# HB_Drive.net
KiCad netlist of a schematic drawn in Altium Designer
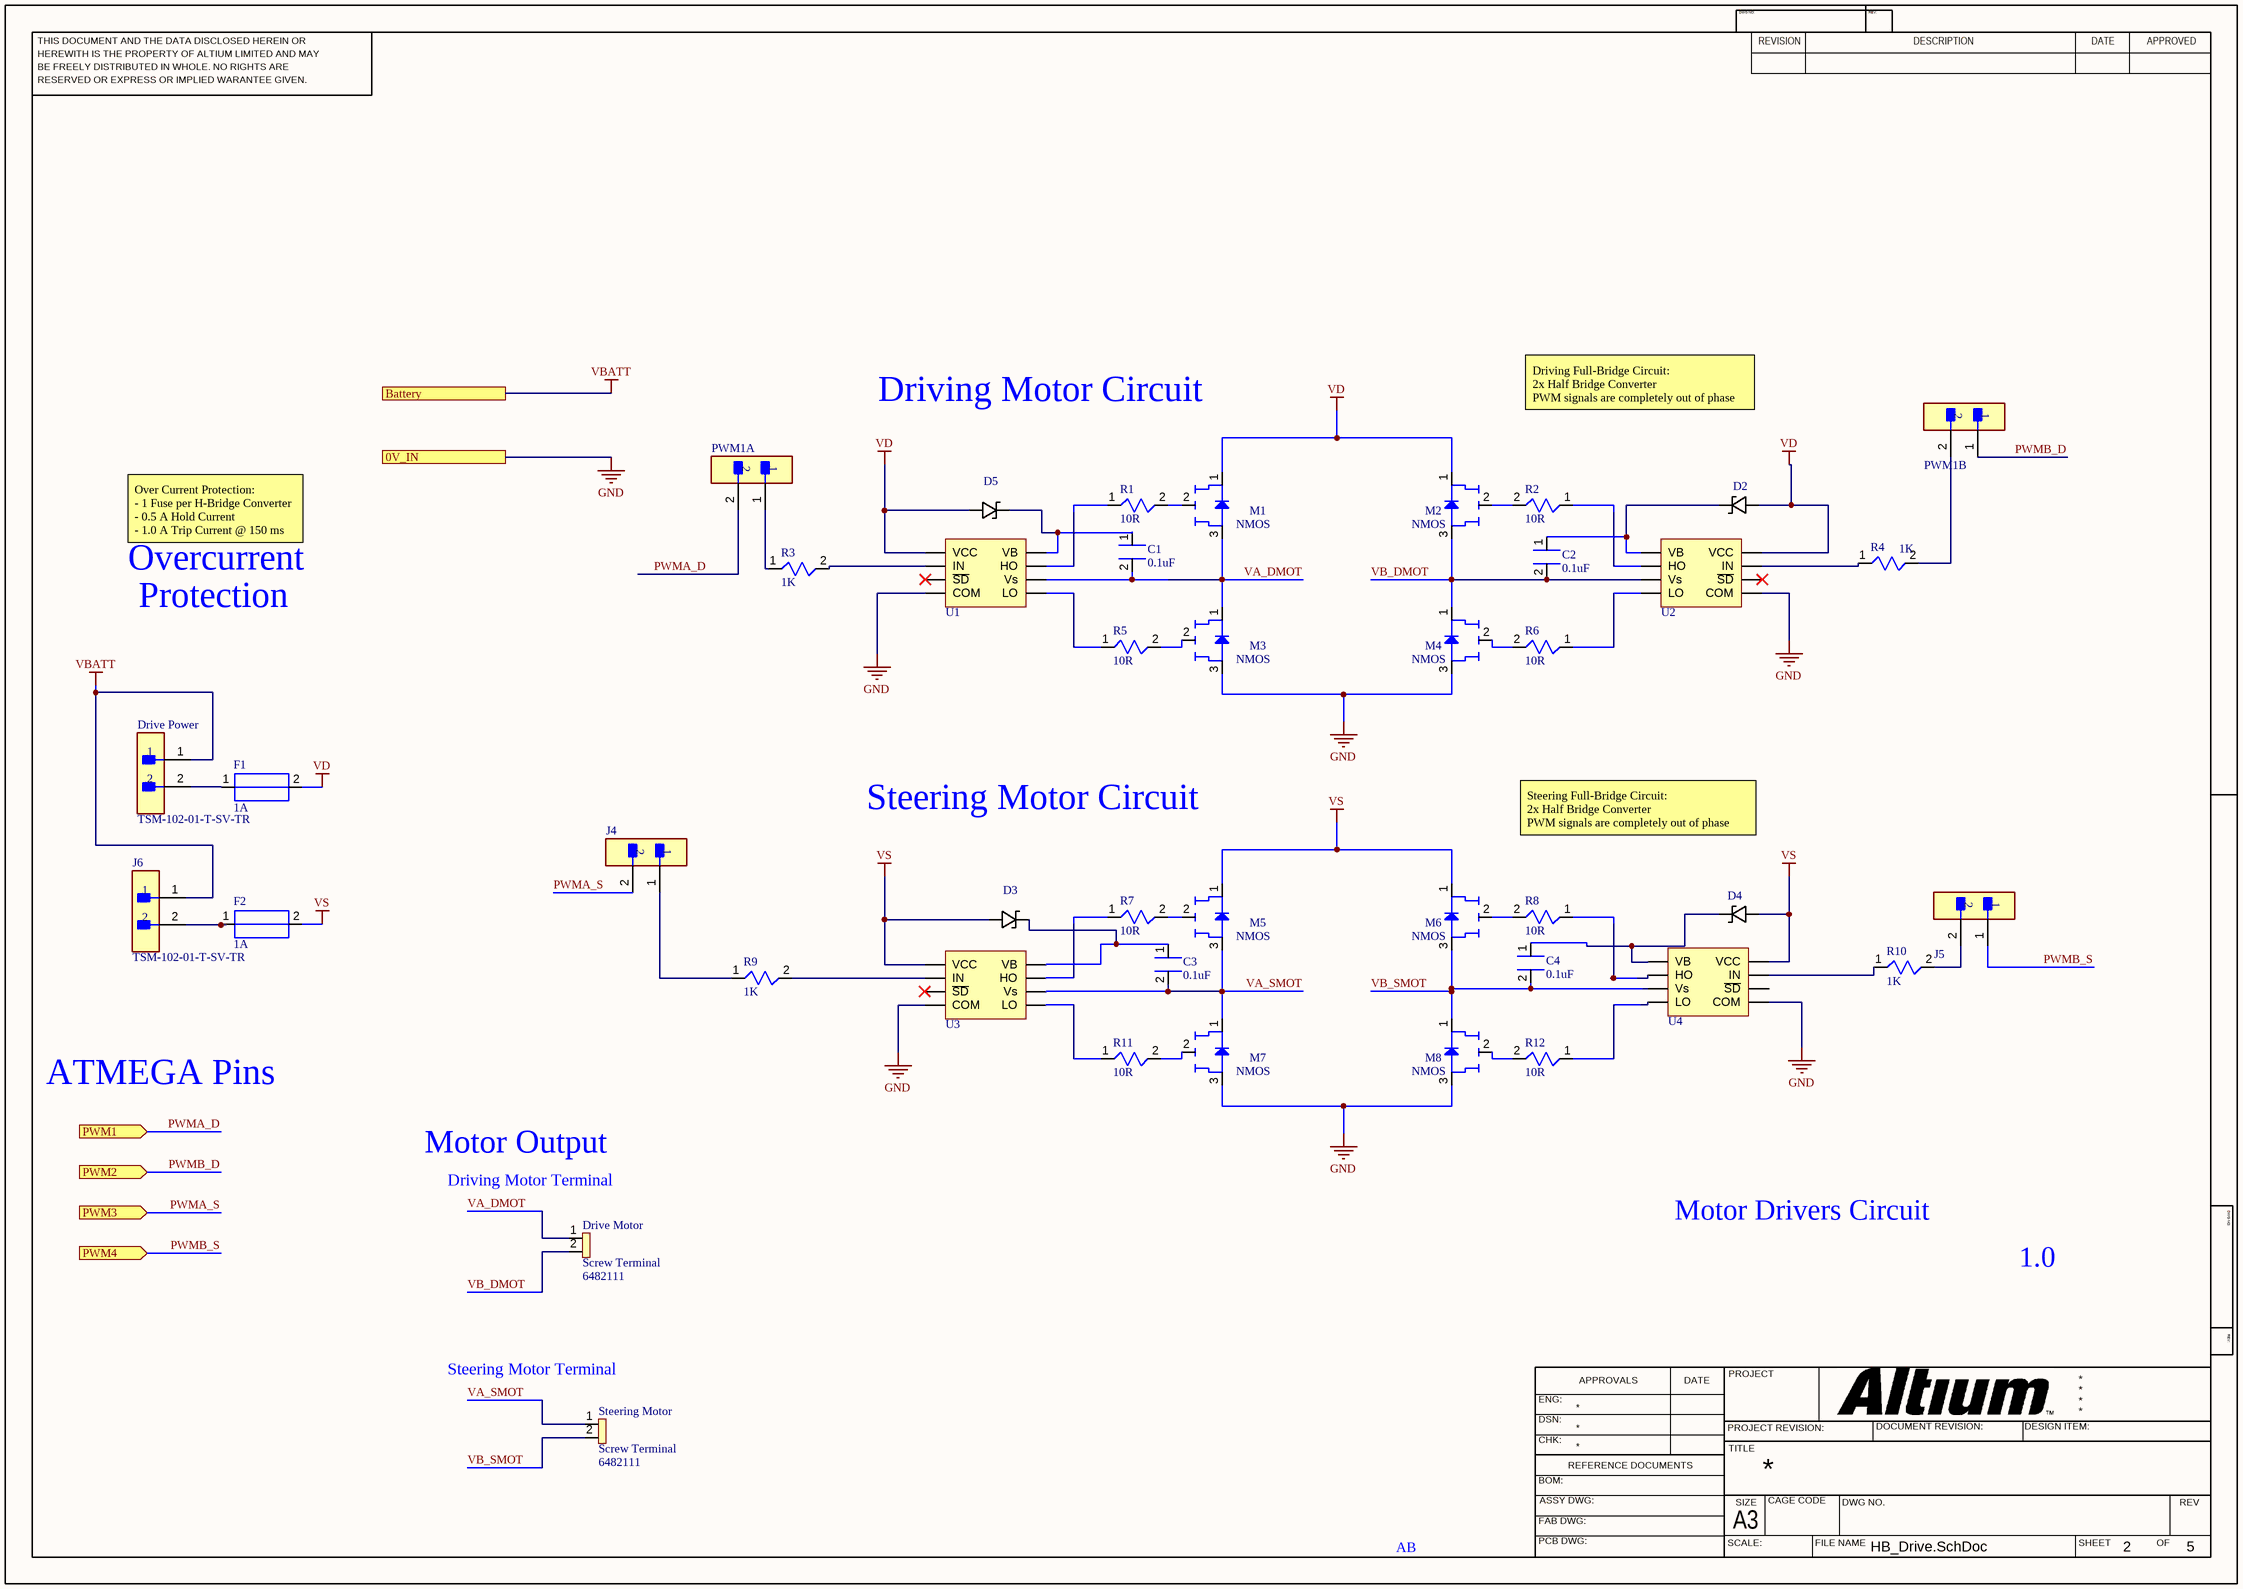
[diagram p0: HB_Drive.SchDoc]

(export (version "E")
  (design (tool "Eeschema 10.0.6"))
  (components
    (comp (ref "C1")
      (value "0.1uF")
      (footprint "0805B104K500BD")
      (description "0.1 uF 50V Cap")
      (libsource (lib "HB_Driver") (part "0805B104K500BD"))
    )
    (comp (ref "C2")
      (value "0.1uF")
      (footprint "0805B104K500BD")
      (description "0.1 uF 50V Cap")
      (libsource (lib "HB_Driver") (part "0805B104K500BD"))
    )
    (comp (ref "C3")
      (value "0.1uF")
      (footprint "0805B104K500BD")
      (description "0.1 uF 50V Cap")
      (libsource (lib "HB_Driver") (part "0805B104K500BD"))
    )
    (comp (ref "C4")
      (value "0.1uF")
      (footprint "0805B104K500BD")
      (description "0.1 uF 50V Cap")
      (libsource (lib "HB_Driver") (part "0805B104K500BD"))
    )
    (comp (ref "D2")
      (value "BAS3005B02VH6327XTSA1")
      (footprint "BAS3005B02VH6327XTSA1")
      (description "30V, Vf 620 mV @ 500 mA, 25 µA @ 30 V, Fast Recovery =< 500ns, > 200mA")
      (libsource (lib "HB_Driver") (part "BAS3005B02VH6327XTSA1"))
    )
    (comp (ref "D3")
      (value "BAS3005B02VH6327XTSA1")
      (footprint "BAS3005B02VH6327XTSA1")
      (description "30V, Vf 620 mV @ 500 mA, 25 µA @ 30 V, Fast Recovery =< 500ns, > 200mA")
      (libsource (lib "HB_Driver") (part "BAS3005B02VH6327XTSA1"))
    )
    (comp (ref "D4")
      (value "BAS3005B02VH6327XTSA1")
      (footprint "BAS3005B02VH6327XTSA1")
      (description "30V, Vf 620 mV @ 500 mA, 25 µA @ 30 V, Fast Recovery =< 500ns, > 200mA")
      (libsource (lib "HB_Driver") (part "BAS3005B02VH6327XTSA1"))
    )
    (comp (ref "D5")
      (value "BAS3005B02VH6327XTSA1")
      (footprint "BAS3005B02VH6327XTSA1")
      (description "30V, Vf 620 mV @ 500 mA, 25 µA @ 30 V, Fast Recovery =< 500ns, > 200mA")
      (libsource (lib "HB_Driver") (part "BAS3005B02VH6327XTSA1"))
    )
    (comp (ref "Drive Motor")
      (value "Screw Terminal")
      (footprint "ERM BLOCK 2POS 45DEG 2.5MM PCB")
      (fields (field (name "SUPPLIER PART NUMBER 1") "6482111"))
      (libsource (lib "HB_Driver") (part "ERM BLOCK 2POS 45DEG 2.5MM PCB"))
    )
    (comp (ref "Drive Power")
      (value "TSM-102-01-T-SV-TR")
      (footprint "FP-TSM-102-01-T-SV-TR-MFG")
      (description "CONN HEADER SMD 2POS 2.54MM")
      (libsource (lib "") (part "3bc925449376181038e59eaffc5286c_1"))
    )
    (comp (ref "F1")
      (value "1A")
      (footprint "0ZCG0050AF2C")
      (description "PTC Resettable Fuse 0.5A(hold) 1A(trip) 30VDC 100A 0.8W 0.15s 0.15Ohm SMD Solder Pad 1812 T/R")
      (fields (field (name "MANUFACTURER") "Bel") (field (name "MANUFACTURER PART NUMBER") "0ZCG0050AF2C"))
      (libsource (lib "HB_Driver") (part "0ZCG0050AF2C"))
    )
    (comp (ref "F2")
      (value "1A")
      (footprint "0ZCG0050AF2C")
      (description "PTC Resettable Fuse 0.5A(hold) 1A(trip) 30VDC 100A 0.8W 0.15s 0.15Ohm SMD Solder Pad 1812 T/R")
      (fields (field (name "MANUFACTURER") "Bel") (field (name "MANUFACTURER PART NUMBER") "0ZCG0050AF2C"))
      (libsource (lib "HB_Driver") (part "0ZCG0050AF2C"))
    )
    (comp (ref "J4")
      (value "TSM-102-01-T-SV-TR")
      (footprint "FP-TSM-102-01-T-SV-TR-MFG")
      (description "CONN HEADER SMD 2POS 2.54MM")
      (libsource (lib "Altium Content Vault") (part "3bc925449376181038e59eaffc5286c"))
    )
    (comp (ref "J5")
      (value "TSM-102-01-T-SV-TR")
      (footprint "FP-TSM-102-01-T-SV-TR-MFG")
      (description "CONN HEADER SMD 2POS 2.54MM")
      (libsource (lib "Altium Content Vault") (part "3bc925449376181038e59eaffc5286c"))
    )
    (comp (ref "J6")
      (value "TSM-102-01-T-SV-TR")
      (footprint "FP-TSM-102-01-T-SV-TR-MFG")
      (description "CONN HEADER SMD 2POS 2.54MM")
      (libsource (lib "") (part "3bc925449376181038e59eaffc5286c_1"))
    )
    (comp (ref "M1")
      (value "NMOS")
      (footprint "AOD424")
      (description "MOSFET N-CH 20V 18A TO252")
      (fields
        (field (name "MANUFACTURER") "Alpha & Omega Semiconductor")
        (field (name "MANUFACTURER PART NUMBER") "AOD424")
      )
      (libsource (lib "HB_Driver") (part "AOD424"))
    )
    (comp (ref "M2")
      (value "NMOS")
      (footprint "AOD424")
      (description "MOSFET N-CH 20V 18A TO252")
      (fields
        (field (name "MANUFACTURER") "Alpha & Omega Semiconductor")
        (field (name "MANUFACTURER PART NUMBER") "AOD424")
      )
      (libsource (lib "HB_Driver") (part "AOD424"))
    )
    (comp (ref "M3")
      (value "NMOS")
      (footprint "AOD424")
      (description "MOSFET N-CH 20V 18A TO252")
      (fields
        (field (name "MANUFACTURER") "Alpha & Omega Semiconductor")
        (field (name "MANUFACTURER PART NUMBER") "AOD424")
      )
      (libsource (lib "HB_Driver") (part "AOD424"))
    )
    (comp (ref "M4")
      (value "NMOS")
      (footprint "AOD424")
      (description "MOSFET N-CH 20V 18A TO252")
      (fields
        (field (name "MANUFACTURER") "Alpha & Omega Semiconductor")
        (field (name "MANUFACTURER PART NUMBER") "AOD424")
      )
      (libsource (lib "HB_Driver") (part "AOD424"))
    )
    (comp (ref "M5")
      (value "NMOS")
      (footprint "AOD424")
      (description "MOSFET N-CH 20V 18A TO252")
      (fields
        (field (name "MANUFACTURER") "Alpha & Omega Semiconductor")
        (field (name "MANUFACTURER PART NUMBER") "AOD424")
      )
      (libsource (lib "HB_Driver") (part "AOD424"))
    )
    (comp (ref "M6")
      (value "NMOS")
      (footprint "AOD424")
      (description "MOSFET N-CH 20V 18A TO252")
      (fields
        (field (name "MANUFACTURER") "Alpha & Omega Semiconductor")
        (field (name "MANUFACTURER PART NUMBER") "AOD424")
      )
      (libsource (lib "HB_Driver") (part "AOD424"))
    )
    (comp (ref "M7")
      (value "NMOS")
      (footprint "AOD424")
      (description "MOSFET N-CH 20V 18A TO252")
      (fields
        (field (name "MANUFACTURER") "Alpha & Omega Semiconductor")
        (field (name "MANUFACTURER PART NUMBER") "AOD424")
      )
      (libsource (lib "HB_Driver") (part "AOD424"))
    )
    (comp (ref "M8")
      (value "NMOS")
      (footprint "AOD424")
      (description "MOSFET N-CH 20V 18A TO252")
      (fields
        (field (name "MANUFACTURER") "Alpha & Omega Semiconductor")
        (field (name "MANUFACTURER PART NUMBER") "AOD424")
      )
      (libsource (lib "HB_Driver") (part "AOD424"))
    )
    (comp (ref "PWM1A")
      (value "TSM-102-01-T-SV-TR")
      (footprint "FP-TSM-102-01-T-SV-TR-MFG")
      (description "CONN HEADER SMD 2POS 2.54MM")
      (libsource (lib "Altium Content Vault") (part "3bc925449376181038e59eaffc5286c"))
    )
    (comp (ref "PWM1B")
      (value "TSM-102-01-T-SV-TR")
      (footprint "FP-TSM-102-01-T-SV-TR-MFG")
      (description "CONN HEADER SMD 2POS 2.54MM")
      (libsource (lib "Altium Content Vault") (part "3bc925449376181038e59eaffc5286c"))
    )
    (comp (ref "R1")
      (value "10R")
      (footprint "RNCP0805FTD10R0")
      (description "RES 10 OHM 1% 1/4W 0805")
      (fields
        (field (name "MANUFACTURER") "Stackpole Electronics")
        (field (name "MANUFACTURER PART NUMBER") "RNCP0805FTD10R0")
      )
      (libsource (lib "HB_Driver") (part "RNCP0805FTD10R0"))
    )
    (comp (ref "R2")
      (value "10R")
      (footprint "RNCP0805FTD10R0")
      (description "RES 10 OHM 1% 1/4W 0805")
      (fields
        (field (name "MANUFACTURER") "Stackpole Electronics")
        (field (name "MANUFACTURER PART NUMBER") "RNCP0805FTD10R0")
      )
      (libsource (lib "HB_Driver") (part "RNCP0805FTD10R0"))
    )
    (comp (ref "R3")
      (value "1K")
      (footprint "RNCP0805FTD10R0")
      (description "Res Thin Film 0805 1K Ohm 1% 0.25W(1/4W) ±100ppm/C Sulfur Resistant Pad SMD T/R")
      (fields
        (field (name "MANUFACTURER") "Stackpole Electronics")
        (field (name "MANUFACTURER PART NUMBER") "RNCP0805FTD1K00")
      )
      (libsource (lib "HB_Driver") (part "RNCP0805FTD1K00"))
    )
    (comp (ref "R4")
      (value "1K")
      (footprint "RNCP0805FTD10R0")
      (description "Res Thin Film 0805 1K Ohm 1% 0.25W(1/4W) ±100ppm/C Sulfur Resistant Pad SMD T/R")
      (fields
        (field (name "MANUFACTURER") "Stackpole Electronics")
        (field (name "MANUFACTURER PART NUMBER") "RNCP0805FTD1K00")
      )
      (libsource (lib "HB_Driver") (part "RNCP0805FTD1K00"))
    )
    (comp (ref "R5")
      (value "10R")
      (footprint "RNCP0805FTD10R0")
      (description "RES 10 OHM 1% 1/4W 0805")
      (fields
        (field (name "MANUFACTURER") "Stackpole Electronics")
        (field (name "MANUFACTURER PART NUMBER") "RNCP0805FTD10R0")
      )
      (libsource (lib "HB_Driver") (part "RNCP0805FTD10R0"))
    )
    (comp (ref "R6")
      (value "10R")
      (footprint "RNCP0805FTD10R0")
      (description "RES 10 OHM 1% 1/4W 0805")
      (fields
        (field (name "MANUFACTURER") "Stackpole Electronics")
        (field (name "MANUFACTURER PART NUMBER") "RNCP0805FTD10R0")
      )
      (libsource (lib "HB_Driver") (part "RNCP0805FTD10R0"))
    )
    (comp (ref "R7")
      (value "10R")
      (footprint "RNCP0805FTD10R0")
      (description "RES 10 OHM 1% 1/4W 0805")
      (fields
        (field (name "MANUFACTURER") "Stackpole Electronics")
        (field (name "MANUFACTURER PART NUMBER") "RNCP0805FTD10R0")
      )
      (libsource (lib "HB_Driver") (part "RNCP0805FTD10R0"))
    )
    (comp (ref "R8")
      (value "10R")
      (footprint "RNCP0805FTD10R0")
      (description "RES 10 OHM 1% 1/4W 0805")
      (fields
        (field (name "MANUFACTURER") "Stackpole Electronics")
        (field (name "MANUFACTURER PART NUMBER") "RNCP0805FTD10R0")
      )
      (libsource (lib "HB_Driver") (part "RNCP0805FTD10R0"))
    )
    (comp (ref "R9")
      (value "1K")
      (footprint "RNCP0805FTD10R0")
      (description "Res Thin Film 0805 1K Ohm 1% 0.25W(1/4W) ±100ppm/C Sulfur Resistant Pad SMD T/R")
      (fields
        (field (name "MANUFACTURER") "Stackpole Electronics")
        (field (name "MANUFACTURER PART NUMBER") "RNCP0805FTD1K00")
      )
      (libsource (lib "HB_Driver") (part "RNCP0805FTD1K00"))
    )
    (comp (ref "R10")
      (value "1K")
      (footprint "RNCP0805FTD10R0")
      (description "Res Thin Film 0805 1K Ohm 1% 0.25W(1/4W) ±100ppm/C Sulfur Resistant Pad SMD T/R")
      (fields
        (field (name "MANUFACTURER") "Stackpole Electronics")
        (field (name "MANUFACTURER PART NUMBER") "RNCP0805FTD1K00")
      )
      (libsource (lib "HB_Driver") (part "RNCP0805FTD1K00"))
    )
    (comp (ref "R11")
      (value "10R")
      (footprint "RNCP0805FTD10R0")
      (description "RES 10 OHM 1% 1/4W 0805")
      (fields
        (field (name "MANUFACTURER") "Stackpole Electronics")
        (field (name "MANUFACTURER PART NUMBER") "RNCP0805FTD10R0")
      )
      (libsource (lib "HB_Driver") (part "RNCP0805FTD10R0"))
    )
    (comp (ref "R12")
      (value "10R")
      (footprint "RNCP0805FTD10R0")
      (description "RES 10 OHM 1% 1/4W 0805")
      (fields
        (field (name "MANUFACTURER") "Stackpole Electronics")
        (field (name "MANUFACTURER PART NUMBER") "RNCP0805FTD10R0")
      )
      (libsource (lib "HB_Driver") (part "RNCP0805FTD10R0"))
    )
    (comp (ref "Steering Motor")
      (value "Screw Terminal")
      (footprint "ERM BLOCK 2POS 45DEG 2.5MM PCB")
      (fields (field (name "SUPPLIER PART NUMBER 1") "6482111"))
      (libsource (lib "HB_Driver") (part "ERM BLOCK 2POS 45DEG 2.5MM PCB"))
    )
    (comp (ref "U1") (value "IR2302") (footprint "IR2302S") (libsource (lib "HB_Driver") (part "IR2302")))
    (comp (ref "U2") (value "IR2302") (footprint "IR2302S") (libsource (lib "") (part "IR2302_1")))
    (comp (ref "U3") (value "IR2302") (footprint "IR2302S") (libsource (lib "HB_Driver") (part "IR2302")))
    (comp (ref "U4") (value "IR2302") (footprint "IR2302S") (libsource (lib "") (part "IR2302_1")))
  )
  (nets
    (net (code "1") (name "/PWMA_D") (class "Default")
      (node (ref "PWM1A") (pin "2") (pinfunction "2_2") (pintype "passive"))
    )
    (net (code "2") (name "/PWMA_S") (class "Default")
      (node (ref "J4") (pin "2") (pinfunction "2_2") (pintype "passive"))
    )
    (net (code "3") (name "/PWMB_D") (class "Default")
      (node (ref "PWM1B") (pin "1") (pinfunction "1_1") (pintype "passive"))
    )
    (net (code "4") (name "/PWMB_S") (class "Default")
      (node (ref "J5") (pin "1") (pinfunction "1_1") (pintype "passive"))
    )
    (net (code "5") (name "/VA_DMOT") (class "Default")
      (node (ref "C1") (pin "2") (pinfunction "2_2") (pintype "passive"))
      (node (ref "Drive Motor") (pin "1") (pinfunction "0_1") (pintype "passive"))
      (node (ref "M1") (pin "3") (pinfunction "S_3") (pintype "passive"))
      (node (ref "M3") (pin "1") (pinfunction "D_1") (pintype "passive"))
      (node (ref "U1") (pin "6") (pinfunction "Vs_6") (pintype "passive"))
    )
    (net (code "6") (name "/VA_SMOT") (class "Default")
      (node (ref "C3") (pin "2") (pinfunction "2_2") (pintype "passive"))
      (node (ref "M5") (pin "3") (pinfunction "S_3") (pintype "passive"))
      (node (ref "M7") (pin "1") (pinfunction "D_1") (pintype "passive"))
      (node (ref "Steering Motor") (pin "1") (pinfunction "0_1") (pintype "passive"))
      (node (ref "U3") (pin "6") (pinfunction "Vs_6") (pintype "passive"))
    )
    (net (code "7") (name "/VB_DMOT") (class "Default")
      (node (ref "C2") (pin "2") (pinfunction "2_2") (pintype "passive"))
      (node (ref "Drive Motor") (pin "2") (pinfunction "2_2") (pintype "passive"))
      (node (ref "M2") (pin "3") (pinfunction "S_3") (pintype "passive"))
      (node (ref "M4") (pin "1") (pinfunction "D_1") (pintype "passive"))
      (node (ref "U2") (pin "6") (pinfunction "Vs_6") (pintype "passive"))
    )
    (net (code "8") (name "/VB_SMOT") (class "Default")
      (node (ref "C4") (pin "2") (pinfunction "2_2") (pintype "passive"))
      (node (ref "M6") (pin "3") (pinfunction "S_3") (pintype "passive"))
      (node (ref "M8") (pin "1") (pinfunction "D_1") (pintype "passive"))
      (node (ref "Steering Motor") (pin "2") (pinfunction "2_2") (pintype "passive"))
      (node (ref "U4") (pin "6") (pinfunction "Vs_6") (pintype "passive"))
    )
    (net (code "9") (name "GND") (class "Default")
      (node (ref "M3") (pin "3") (pinfunction "S_3") (pintype "passive"))
      (node (ref "M4") (pin "3") (pinfunction "S_3") (pintype "passive"))
      (node (ref "M7") (pin "3") (pinfunction "S_3") (pintype "passive"))
      (node (ref "M8") (pin "3") (pinfunction "S_3") (pintype "passive"))
      (node (ref "U1") (pin "4") (pinfunction "COM_4") (pintype "passive"))
      (node (ref "U2") (pin "4") (pinfunction "COM_4") (pintype "passive"))
      (node (ref "U3") (pin "4") (pinfunction "COM_4") (pintype "passive"))
      (node (ref "U4") (pin "4") (pinfunction "COM_4") (pintype "passive"))
    )
    (net (code "10") (name "Net-(C1-+)") (class "Default")
      (node (ref "C1") (pin "1") (pinfunction "+_1") (pintype "passive"))
      (node (ref "D5") (pin "2") (pinfunction "2_2") (pintype "passive"))
      (node (ref "U1") (pin "8") (pinfunction "VB_8") (pintype "passive"))
    )
    (net (code "11") (name "Net-(C2-+)") (class "Default")
      (node (ref "C2") (pin "1") (pinfunction "+_1") (pintype "passive"))
      (node (ref "D2") (pin "2") (pinfunction "2_2") (pintype "passive"))
      (node (ref "U2") (pin "8") (pinfunction "VB_8") (pintype "passive"))
    )
    (net (code "12") (name "Net-(C3-+)") (class "Default")
      (node (ref "C3") (pin "1") (pinfunction "+_1") (pintype "passive"))
      (node (ref "D3") (pin "2") (pinfunction "2_2") (pintype "passive"))
      (node (ref "U3") (pin "8") (pinfunction "VB_8") (pintype "passive"))
    )
    (net (code "13") (name "Net-(C4-+)") (class "Default")
      (node (ref "C4") (pin "1") (pinfunction "+_1") (pintype "passive"))
      (node (ref "D4") (pin "2") (pinfunction "2_2") (pintype "passive"))
      (node (ref "U4") (pin "8") (pinfunction "VB_8") (pintype "passive"))
    )
    (net (code "14") (name "Net-(F1-+)") (class "Default")
      (node (ref "Drive Power") (pin "2") (pinfunction "2_2") (pintype "passive"))
      (node (ref "F1") (pin "1") (pinfunction "+_1") (pintype "passive"))
    )
    (net (code "15") (name "Net-(F2-+)") (class "Default")
      (node (ref "F2") (pin "1") (pinfunction "+_1") (pintype "passive"))
      (node (ref "J6") (pin "2") (pinfunction "2_2") (pintype "passive"))
    )
    (net (code "16") (name "Net-(M1-G)") (class "Default")
      (node (ref "M1") (pin "2") (pinfunction "G_2") (pintype "passive"))
      (node (ref "R1") (pin "2") (pinfunction "-_2") (pintype "passive"))
    )
    (net (code "17") (name "Net-(M2-G)") (class "Default")
      (node (ref "M2") (pin "2") (pinfunction "G_2") (pintype "passive"))
      (node (ref "R2") (pin "2") (pinfunction "-_2") (pintype "passive"))
    )
    (net (code "18") (name "Net-(M3-G)") (class "Default")
      (node (ref "M3") (pin "2") (pinfunction "G_2") (pintype "passive"))
      (node (ref "R5") (pin "2") (pinfunction "-_2") (pintype "passive"))
    )
    (net (code "19") (name "Net-(M4-G)") (class "Default")
      (node (ref "M4") (pin "2") (pinfunction "G_2") (pintype "passive"))
      (node (ref "R6") (pin "2") (pinfunction "-_2") (pintype "passive"))
    )
    (net (code "20") (name "Net-(M5-G)") (class "Default")
      (node (ref "M5") (pin "2") (pinfunction "G_2") (pintype "passive"))
      (node (ref "R7") (pin "2") (pinfunction "-_2") (pintype "passive"))
    )
    (net (code "21") (name "Net-(M6-G)") (class "Default")
      (node (ref "M6") (pin "2") (pinfunction "G_2") (pintype "passive"))
      (node (ref "R8") (pin "2") (pinfunction "-_2") (pintype "passive"))
    )
    (net (code "22") (name "Net-(M7-G)") (class "Default")
      (node (ref "M7") (pin "2") (pinfunction "G_2") (pintype "passive"))
      (node (ref "R11") (pin "2") (pinfunction "-_2") (pintype "passive"))
    )
    (net (code "23") (name "Net-(M8-G)") (class "Default")
      (node (ref "M8") (pin "2") (pinfunction "G_2") (pintype "passive"))
      (node (ref "R12") (pin "2") (pinfunction "-_2") (pintype "passive"))
    )
    (net (code "24") (name "Net-(R1-+)") (class "Default")
      (node (ref "R1") (pin "1") (pinfunction "+_1") (pintype "passive"))
      (node (ref "U1") (pin "7") (pinfunction "HO_7") (pintype "passive"))
    )
    (net (code "25") (name "Net-(R2-+)") (class "Default")
      (node (ref "R2") (pin "1") (pinfunction "+_1") (pintype "passive"))
      (node (ref "U2") (pin "7") (pinfunction "HO_7") (pintype "passive"))
    )
    (net (code "26") (name "Net-(R3-+)") (class "Default")
      (node (ref "PWM1A") (pin "1") (pinfunction "1_1") (pintype "passive"))
      (node (ref "R3") (pin "1") (pinfunction "+_1") (pintype "passive"))
    )
    (net (code "27") (name "Net-(R3--)") (class "Default")
      (node (ref "R3") (pin "2") (pinfunction "-_2") (pintype "passive"))
      (node (ref "U1") (pin "2") (pinfunction "IN_2") (pintype "passive"))
    )
    (net (code "28") (name "Net-(R4-+)") (class "Default")
      (node (ref "R4") (pin "1") (pinfunction "+_1") (pintype "passive"))
      (node (ref "U2") (pin "2") (pinfunction "IN_2") (pintype "passive"))
    )
    (net (code "29") (name "Net-(R4--)") (class "Default")
      (node (ref "PWM1B") (pin "2") (pinfunction "2_2") (pintype "passive"))
      (node (ref "R4") (pin "2") (pinfunction "-_2") (pintype "passive"))
    )
    (net (code "30") (name "Net-(R5-+)") (class "Default")
      (node (ref "R5") (pin "1") (pinfunction "+_1") (pintype "passive"))
      (node (ref "U1") (pin "5") (pinfunction "LO_5") (pintype "passive"))
    )
    (net (code "31") (name "Net-(R6-+)") (class "Default")
      (node (ref "R6") (pin "1") (pinfunction "+_1") (pintype "passive"))
      (node (ref "U2") (pin "5") (pinfunction "LO_5") (pintype "passive"))
    )
    (net (code "32") (name "Net-(R7-+)") (class "Default")
      (node (ref "R7") (pin "1") (pinfunction "+_1") (pintype "passive"))
      (node (ref "U3") (pin "7") (pinfunction "HO_7") (pintype "passive"))
    )
    (net (code "33") (name "Net-(R8-+)") (class "Default")
      (node (ref "R8") (pin "1") (pinfunction "+_1") (pintype "passive"))
      (node (ref "U4") (pin "7") (pinfunction "HO_7") (pintype "passive"))
    )
    (net (code "34") (name "Net-(R9-+)") (class "Default")
      (node (ref "J4") (pin "1") (pinfunction "1_1") (pintype "passive"))
      (node (ref "R9") (pin "1") (pinfunction "+_1") (pintype "passive"))
    )
    (net (code "35") (name "Net-(R9--)") (class "Default")
      (node (ref "R9") (pin "2") (pinfunction "-_2") (pintype "passive"))
      (node (ref "U3") (pin "2") (pinfunction "IN_2") (pintype "passive"))
    )
    (net (code "36") (name "Net-(R10-+)") (class "Default")
      (node (ref "R10") (pin "1") (pinfunction "+_1") (pintype "passive"))
      (node (ref "U4") (pin "2") (pinfunction "IN_2") (pintype "passive"))
    )
    (net (code "37") (name "Net-(R10--)") (class "Default")
      (node (ref "J5") (pin "2") (pinfunction "2_2") (pintype "passive"))
      (node (ref "R10") (pin "2") (pinfunction "-_2") (pintype "passive"))
    )
    (net (code "38") (name "Net-(R11-+)") (class "Default")
      (node (ref "R11") (pin "1") (pinfunction "+_1") (pintype "passive"))
      (node (ref "U3") (pin "5") (pinfunction "LO_5") (pintype "passive"))
    )
    (net (code "39") (name "Net-(R12-+)") (class "Default")
      (node (ref "R12") (pin "1") (pinfunction "+_1") (pintype "passive"))
      (node (ref "U4") (pin "5") (pinfunction "LO_5") (pintype "passive"))
    )
    (net (code "40") (name "VBATT") (class "Default")
      (node (ref "Drive Power") (pin "1") (pinfunction "1_1") (pintype "passive"))
      (node (ref "J6") (pin "1") (pinfunction "1_1") (pintype "passive"))
    )
    (net (code "41") (name "VD") (class "Default")
      (node (ref "D2") (pin "1") (pinfunction "1_1") (pintype "passive"))
      (node (ref "D5") (pin "1") (pinfunction "1_1") (pintype "passive"))
      (node (ref "F1") (pin "2") (pinfunction "-_2") (pintype "passive"))
      (node (ref "M1") (pin "1") (pinfunction "D_1") (pintype "passive"))
      (node (ref "M2") (pin "1") (pinfunction "D_1") (pintype "passive"))
      (node (ref "U1") (pin "1") (pinfunction "VCC_1") (pintype "passive"))
      (node (ref "U2") (pin "1") (pinfunction "VCC_1") (pintype "passive"))
    )
    (net (code "42") (name "VS") (class "Default")
      (node (ref "D3") (pin "1") (pinfunction "1_1") (pintype "passive"))
      (node (ref "D4") (pin "1") (pinfunction "1_1") (pintype "passive"))
      (node (ref "F2") (pin "2") (pinfunction "-_2") (pintype "passive"))
      (node (ref "M5") (pin "1") (pinfunction "D_1") (pintype "passive"))
      (node (ref "M6") (pin "1") (pinfunction "D_1") (pintype "passive"))
      (node (ref "U3") (pin "1") (pinfunction "VCC_1") (pintype "passive"))
      (node (ref "U4") (pin "1") (pinfunction "VCC_1") (pintype "passive"))
    )
    (net (code "43") (name "unconnected-(U1-~{SD}-Pad3)") (class "Default")
      (node (ref "U1") (pin "3") (pinfunction "~{SD}_3") (pintype "passive+no_connect"))
    )
    (net (code "44") (name "unconnected-(U2-~{SD}-Pad3)") (class "Default")
      (node (ref "U2") (pin "3") (pinfunction "~{SD}_3") (pintype "passive+no_connect"))
    )
    (net (code "45") (name "unconnected-(U3-~{SD}-Pad3)") (class "Default")
      (node (ref "U3") (pin "3") (pinfunction "~{SD}_3") (pintype "passive+no_connect"))
    )
    (net (code "46") (name "unconnected-(U4-~{SD}-Pad3)") (class "Default")
      (node (ref "U4") (pin "3") (pinfunction "~{SD}_3") (pintype "passive"))
    )
  )
)
